# microcontrollerOptical.net
KiCad netlist of a schematic drawn in Altium Designer
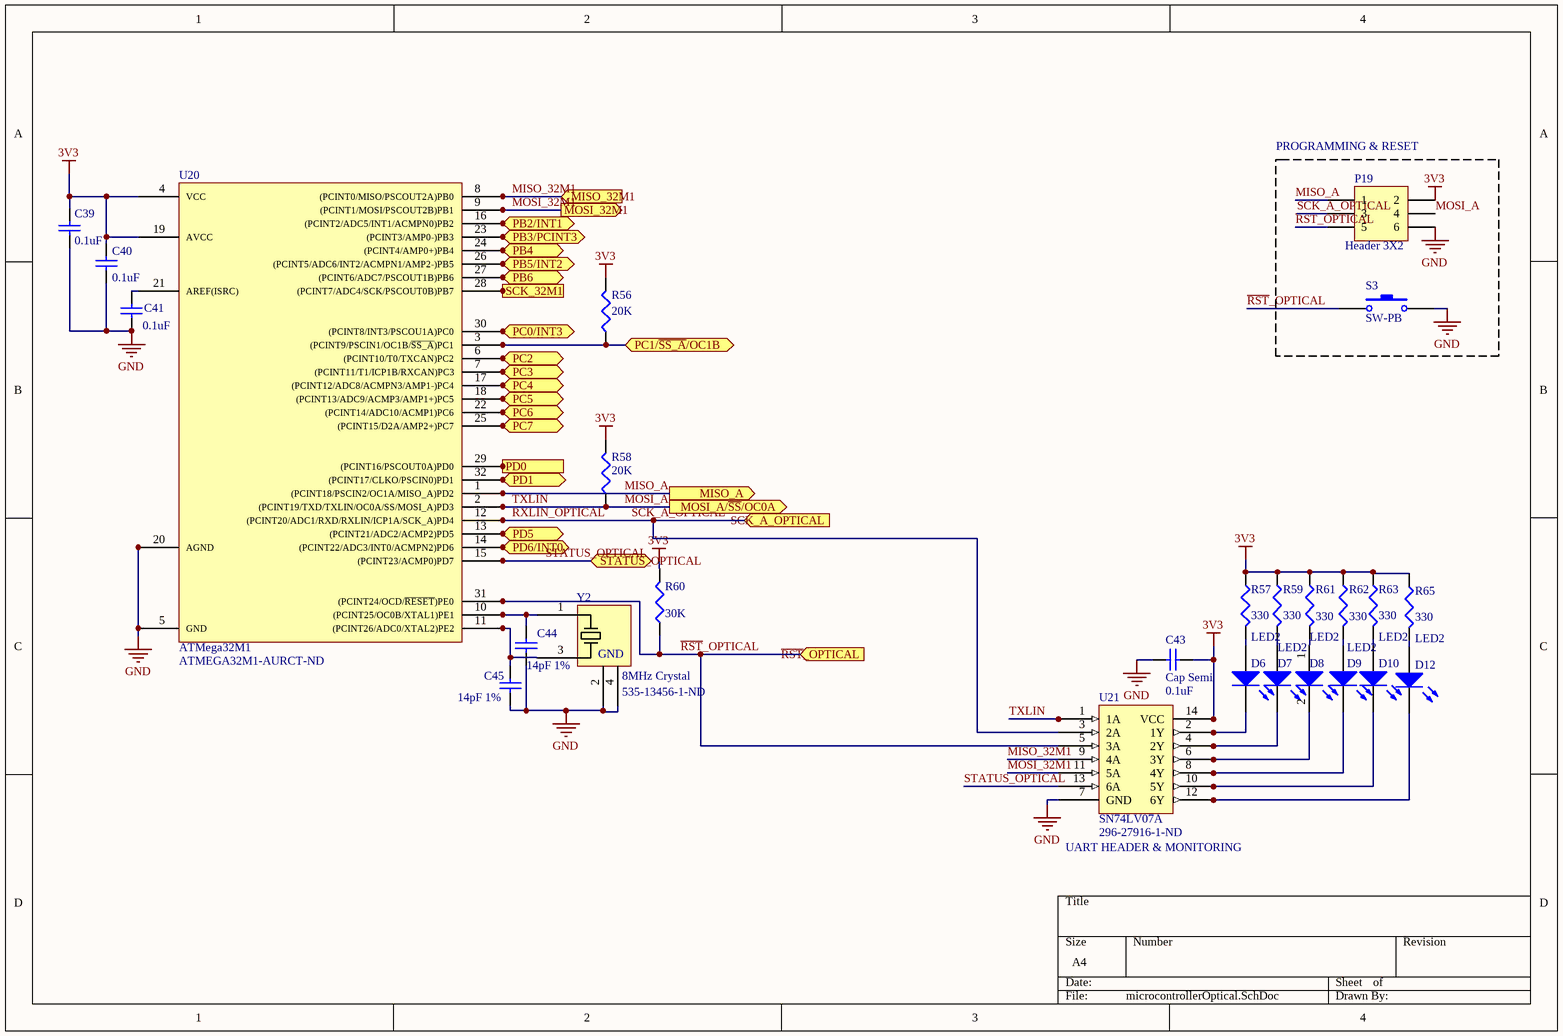
[diagram p0: microcontrollerOptical.SchDoc]

(export (version "E")
  (design (tool "Eeschema 10.0.6"))
  (components
    (comp (ref "C39")
      (value "0.1uF")
      (footprint "1608[0603]")
      (description "Capacitor (Semiconductor SIM Model)")
      (fields (field (name "PUBLISHER") "Altium Limited"))
      (libsource (lib "Miscellaneous Devices") (part "Cap Semi"))
    )
    (comp (ref "C40")
      (value "0.1uF")
      (footprint "1608[0603]")
      (description "Capacitor (Semiconductor SIM Model)")
      (fields (field (name "PUBLISHER") "Altium Limited"))
      (libsource (lib "Miscellaneous Devices") (part "Cap Semi"))
    )
    (comp (ref "C41")
      (value "0.1uF")
      (footprint "1608[0603]")
      (description "Capacitor (Semiconductor SIM Model)")
      (fields (field (name "PUBLISHER") "Altium Limited"))
      (libsource (lib "Miscellaneous Devices") (part "Cap Semi"))
    )
    (comp (ref "C43")
      (value "Cap Semi")
      (footprint "1608[0603]")
      (description "Capacitor (Semiconductor SIM Model)")
      (fields (field (name "ALTIUM_VALUE") "0.1uF") (field (name "PUBLISHER") "Altium Limited"))
      (libsource (lib "Miscellaneous Devices") (part "Cap Semi"))
    )
    (comp (ref "C44")
      (value "14pF 1%")
      (footprint "1608[0603]")
      (description "Capacitor (Semiconductor SIM Model)")
      (fields (field (name "Comment") "15pF 1%") (field (name "PUBLISHER") "Altium Limited"))
      (libsource (lib "Miscellaneous Devices") (part "Cap Semi"))
    )
    (comp (ref "C45")
      (value "14pF 1%")
      (footprint "1608[0603]")
      (description "Capacitor (Semiconductor SIM Model)")
      (fields (field (name "Comment") "15pF 1%") (field (name "PUBLISHER") "Altium Limited"))
      (libsource (lib "Miscellaneous Devices") (part "Cap Semi"))
    )
    (comp (ref "D6")
      (value "LED2")
      (footprint "0603-LED")
      (description "Typical RED, GREEN, YELLOW, AMBER GaAs LED")
      (fields (field (name "PUBLISHER") "Altium Limited"))
      (libsource (lib "") (part "LED2_1"))
    )
    (comp (ref "D7")
      (value "LED2")
      (footprint "0603-LED")
      (description "Typical RED, GREEN, YELLOW, AMBER GaAs LED")
      (fields (field (name "PUBLISHER") "Altium Limited"))
      (libsource (lib "") (part "LED2_1"))
    )
    (comp (ref "D8")
      (value "LED2")
      (footprint "0603-LED")
      (description "Typical RED, GREEN, YELLOW, AMBER GaAs LED")
      (fields (field (name "PUBLISHER") "Altium Limited"))
      (libsource (lib "Miscellaneous Devices") (part "LED2"))
    )
    (comp (ref "D9")
      (value "LED2")
      (footprint "0603-LED")
      (description "Typical RED, GREEN, YELLOW, AMBER GaAs LED")
      (fields (field (name "PUBLISHER") "Altium Limited"))
      (libsource (lib "") (part "LED2_1"))
    )
    (comp (ref "D10")
      (value "LED2")
      (footprint "0603-LED")
      (description "Typical RED, GREEN, YELLOW, AMBER GaAs LED")
      (fields (field (name "PUBLISHER") "Altium Limited"))
      (libsource (lib "") (part "LED2_1"))
    )
    (comp (ref "D12")
      (value "LED2")
      (footprint "0603-LED")
      (description "Typical RED, GREEN, YELLOW, AMBER GaAs LED")
      (fields (field (name "PUBLISHER") "Altium Limited"))
      (libsource (lib "") (part "LED2_1"))
    )
    (comp (ref "P19")
      (value "Header 3X2")
      (footprint "HDR2X3")
      (description "Header, 3-Pin, Dual row")
      (fields (field (name "PUBLISHER") "Altium Limited"))
      (libsource (lib "Miscellaneous Connectors") (part "Header 3X2"))
    )
    (comp (ref "R56")
      (value "20K")
      (footprint "J1-0603")
      (description "Resistor")
      (fields (field (name "PUBLISHER") "Altium Limited"))
      (libsource (lib "Miscellaneous Devices") (part "Res3"))
    )
    (comp (ref "R57")
      (value "330")
      (footprint "J1-0603")
      (description "Resistor")
      (fields (field (name "PUBLISHER") "Altium Limited"))
      (libsource (lib "Miscellaneous Devices") (part "Res3"))
    )
    (comp (ref "R58")
      (value "20K")
      (footprint "J1-0603")
      (description "Resistor")
      (fields (field (name "PUBLISHER") "Altium Limited"))
      (libsource (lib "Miscellaneous Devices") (part "Res3"))
    )
    (comp (ref "R59")
      (value "330")
      (footprint "J1-0603")
      (description "Resistor")
      (fields (field (name "PUBLISHER") "Altium Limited"))
      (libsource (lib "Miscellaneous Devices") (part "Res3"))
    )
    (comp (ref "R60")
      (value "30K")
      (footprint "J1-0603")
      (description "Resistor")
      (fields (field (name "PUBLISHER") "Altium Limited"))
      (libsource (lib "Miscellaneous Devices") (part "Res3"))
    )
    (comp (ref "R61")
      (value "330")
      (footprint "J1-0603")
      (description "Resistor")
      (fields (field (name "PUBLISHER") "Altium Limited"))
      (libsource (lib "Miscellaneous Devices") (part "Res3"))
    )
    (comp (ref "R62")
      (value "330")
      (footprint "J1-0603")
      (description "Resistor")
      (fields (field (name "PUBLISHER") "Altium Limited"))
      (libsource (lib "Miscellaneous Devices") (part "Res3"))
    )
    (comp (ref "R63")
      (value "330")
      (footprint "J1-0603")
      (description "Resistor")
      (fields (field (name "PUBLISHER") "Altium Limited"))
      (libsource (lib "Miscellaneous Devices") (part "Res3"))
    )
    (comp (ref "R65")
      (value "330")
      (footprint "J1-0603")
      (description "Resistor")
      (fields (field (name "PUBLISHER") "Altium Limited"))
      (libsource (lib "Miscellaneous Devices") (part "Res3"))
    )
    (comp (ref "S3")
      (value "SW-PB")
      (footprint "Pushbutton")
      (description "Switch")
      (fields (field (name "PUBLISHER") "Altium Limited"))
      (libsource (lib "Miscellaneous Devices") (part "SW-PB"))
    )
    (comp (ref "U20")
      (value "ATMega32M1")
      (footprint "QFP80P900X900X120-32N")
      (description "Atmel 8-bit AVR microcontroller.")
      (fields (field (name "SUPPLIER PART NUMBER 1") "ATMEGA32M1-AURCT-ND"))
      (libsource (lib "ICs") (part "ATMega32M1"))
    )
    (comp (ref "U21")
      (value "SN74LV07A")
      (footprint "SOP65P640X120-14N")
      (description "Six element 1-bit non-inverting open-drain buffer.")
      (fields (field (name "SUPPLIER PART NUMBER") "296-27916-1-ND"))
      (libsource (lib "ICs") (part "SN74LV07A"))
    )
    (comp (ref "Y2")
      (value "8MHz Crystal")
      (footprint "OSCSC500X320X110-4N")
      (description "8MHz Abracom 4-pin crystal.")
      (fields (field (name "SUPPLIER PART NUMBER 1") "535-13456-1-ND"))
      (libsource (lib "ICs") (part "8MHz Abracom 4-Pin Crystal"))
    )
  )
  (nets
    (net (code "1") (name "/MISO_32M1") (class "Default")
      (node (ref "U20") (pin "8") (pinfunction "(PCINT0/MISO/PSCOUT2A)PB0_8") (pintype "passive"))
      (node (ref "U21") (pin "9") (pinfunction "4A_9") (pintype "input"))
    )
    (net (code "2") (name "/MISO_A") (class "Default")
      (node (ref "P19") (pin "1") (pinfunction "1_1") (pintype "passive"))
      (node (ref "U20") (pin "1") (pinfunction "(PCINT18/PSCIN2/OC1A/MISO_A)PD2_1") (pintype "passive"))
    )
    (net (code "3") (name "/MOSI_32M1") (class "Default")
      (node (ref "U20") (pin "9") (pinfunction "(PCINT1/MOSI/PSCOUT2B)PB1_9") (pintype "passive"))
      (node (ref "U21") (pin "11") (pinfunction "5A_11") (pintype "input"))
    )
    (net (code "4") (name "/MOSI_A") (class "Default")
      (node (ref "P19") (pin "4") (pinfunction "4_4") (pintype "passive"))
      (node (ref "R58") (pin "1") (pinfunction "1_1") (pintype "passive"))
      (node (ref "U20") (pin "2") (pinfunction "(PCINT19/TXD/TXLIN/OC0A/SS/MOSI_A)PD3_2") (pintype "passive"))
      (node (ref "U21") (pin "1") (pinfunction "1A_1") (pintype "input"))
    )
    (net (code "5") (name "/PB2{slash}INT1") (class "Default")
      (node (ref "U20") (pin "16") (pinfunction "(PCINT2/ADC5/INT1/ACMPN0)PB2_16") (pintype "passive"))
    )
    (net (code "6") (name "/PB3{slash}PCINT3") (class "Default")
      (node (ref "U20") (pin "23") (pinfunction "(PCINT3/AMP0-)PB3_23") (pintype "passive"))
    )
    (net (code "7") (name "/PB4") (class "Default")
      (node (ref "U20") (pin "24") (pinfunction "(PCINT4/AMP0+)PB4_24") (pintype "passive"))
    )
    (net (code "8") (name "/PB5{slash}INT2") (class "Default")
      (node (ref "U20") (pin "26") (pinfunction "(PCINT5/ADC6/INT2/ACMPN1/AMP2-)PB5_26") (pintype "passive"))
    )
    (net (code "9") (name "/PB6") (class "Default")
      (node (ref "U20") (pin "27") (pinfunction "(PCINT6/ADC7/PSCOUT1B)PB6_27") (pintype "passive"))
    )
    (net (code "10") (name "/PC0{slash}INT3") (class "Default")
      (node (ref "U20") (pin "30") (pinfunction "(PCINT8/INT3/PSCOU1A)PC0_30") (pintype "passive"))
    )
    (net (code "11") (name "/PC1{slash}~{SS_A}{slash}OC1B") (class "Default")
      (node (ref "R56") (pin "1") (pinfunction "1_1") (pintype "passive"))
      (node (ref "U20") (pin "3") (pinfunction "(PCINT9/PSCIN1/OC1B/~{SS_A})PC1_3") (pintype "passive"))
    )
    (net (code "12") (name "/PC2") (class "Default")
      (node (ref "U20") (pin "6") (pinfunction "(PCINT10/T0/TXCAN)PC2_6") (pintype "passive"))
    )
    (net (code "13") (name "/PC3") (class "Default")
      (node (ref "U20") (pin "7") (pinfunction "(PCINT11/T1/ICP1B/RXCAN)PC3_7") (pintype "passive"))
    )
    (net (code "14") (name "/PC4") (class "Default")
      (node (ref "U20") (pin "17") (pinfunction "(PCINT12/ADC8/ACMPN3/AMP1-)PC4_17") (pintype "passive"))
    )
    (net (code "15") (name "/PC5") (class "Default")
      (node (ref "U20") (pin "18") (pinfunction "(PCINT13/ADC9/ACMP3/AMP1+)PC5_18") (pintype "passive"))
    )
    (net (code "16") (name "/PC6") (class "Default")
      (node (ref "U20") (pin "22") (pinfunction "(PCINT14/ADC10/ACMP1)PC6_22") (pintype "passive"))
    )
    (net (code "17") (name "/PC7") (class "Default")
      (node (ref "U20") (pin "25") (pinfunction "(PCINT15/D2A/AMP2+)PC7_25") (pintype "passive"))
    )
    (net (code "18") (name "/PD0") (class "Default")
      (node (ref "U20") (pin "29") (pinfunction "(PCINT16/PSCOUT0A)PD0_29") (pintype "passive"))
    )
    (net (code "19") (name "/PD1") (class "Default")
      (node (ref "U20") (pin "32") (pinfunction "(PCINT17/CLKO/PSCIN0)PD1_32") (pintype "passive"))
    )
    (net (code "20") (name "/PD5") (class "Default")
      (node (ref "U20") (pin "13") (pinfunction "(PCINT21/ADC2/ACMP2)PD5_13") (pintype "passive"))
    )
    (net (code "21") (name "/PD6{slash}INT0") (class "Default")
      (node (ref "U20") (pin "14") (pinfunction "(PCINT22/ADC3/INT0/ACMPN2)PD6_14") (pintype "passive"))
    )
    (net (code "22") (name "/RXLIN_OPTICAL") (class "Default")
      (node (ref "P19") (pin "3") (pinfunction "3_3") (pintype "passive"))
      (node (ref "U20") (pin "12") (pinfunction "(PCINT20/ADC1/RXD/RXLIN/ICP1A/SCK_A)PD4_12") (pintype "passive"))
      (node (ref "U21") (pin "3") (pinfunction "2A_3") (pintype "input"))
    )
    (net (code "23") (name "/SCK_32M1") (class "Default")
      (node (ref "U20") (pin "28") (pinfunction "(PCINT7/ADC4/SCK/PSCOUT0B)PB7_28") (pintype "passive"))
    )
    (net (code "24") (name "/STATUS_OPTICAL") (class "Default")
      (node (ref "U20") (pin "15") (pinfunction "(PCINT23/ACMP0)PD7_15") (pintype "passive"))
      (node (ref "U21") (pin "13") (pinfunction "6A_13") (pintype "input"))
    )
    (net (code "25") (name "/~{RST}_OPTICAL") (class "Default")
      (node (ref "P19") (pin "5") (pinfunction "5_5") (pintype "passive"))
      (node (ref "R60") (pin "1") (pinfunction "1_1") (pintype "passive"))
      (node (ref "S3") (pin "1") (pinfunction "1_1") (pintype "passive"))
      (node (ref "U20") (pin "31") (pinfunction "(PCINT24/OCD/~{RESET})PE0_31") (pintype "passive"))
      (node (ref "U21") (pin "5") (pinfunction "3A_5") (pintype "input"))
    )
    (net (code "26") (name "3V3") (class "Default")
      (node (ref "C39") (pin "2") (pinfunction "2_2") (pintype "passive"))
      (node (ref "C40") (pin "2") (pinfunction "2_2") (pintype "passive"))
      (node (ref "C43") (pin "2") (pinfunction "2_2") (pintype "passive"))
      (node (ref "P19") (pin "2") (pinfunction "2_2") (pintype "passive"))
      (node (ref "R56") (pin "2") (pinfunction "2_2") (pintype "passive"))
      (node (ref "R57") (pin "1") (pinfunction "1_1") (pintype "passive"))
      (node (ref "R58") (pin "2") (pinfunction "2_2") (pintype "passive"))
      (node (ref "R59") (pin "1") (pinfunction "1_1") (pintype "passive"))
      (node (ref "R60") (pin "2") (pinfunction "2_2") (pintype "passive"))
      (node (ref "R61") (pin "1") (pinfunction "1_1") (pintype "passive"))
      (node (ref "R62") (pin "1") (pinfunction "1_1") (pintype "passive"))
      (node (ref "R63") (pin "1") (pinfunction "1_1") (pintype "passive"))
      (node (ref "R65") (pin "1") (pinfunction "1_1") (pintype "passive"))
      (node (ref "U20") (pin "19") (pinfunction "AVCC_19") (pintype "passive"))
      (node (ref "U20") (pin "4") (pinfunction "VCC_4") (pintype "passive"))
      (node (ref "U21") (pin "14") (pinfunction "VCC_14") (pintype "power_in"))
    )
    (net (code "27") (name "GND") (class "Default")
      (node (ref "C39") (pin "1") (pinfunction "1_1") (pintype "passive"))
      (node (ref "C40") (pin "1") (pinfunction "1_1") (pintype "passive"))
      (node (ref "C41") (pin "2") (pinfunction "2_2") (pintype "passive"))
      (node (ref "C43") (pin "1") (pinfunction "1_1") (pintype "passive"))
      (node (ref "C44") (pin "1") (pinfunction "1_1") (pintype "passive"))
      (node (ref "C45") (pin "1") (pinfunction "1_1") (pintype "passive"))
      (node (ref "P19") (pin "6") (pinfunction "6_6") (pintype "passive"))
      (node (ref "S3") (pin "2") (pinfunction "2_2") (pintype "passive"))
      (node (ref "U20") (pin "20") (pinfunction "AGND_20") (pintype "passive"))
      (node (ref "U20") (pin "5") (pinfunction "GND_5") (pintype "passive"))
      (node (ref "U21") (pin "7") (pinfunction "GND_7") (pintype "power_in"))
      (node (ref "Y2") (pin "2") (pinfunction "5_2") (pintype "passive"))
      (node (ref "Y2") (pin "4") (pinfunction "4_4") (pintype "passive"))
    )
    (net (code "28") (name "Net-(D6-A)") (class "Default")
      (node (ref "D6") (pin "1") (pinfunction "A_1") (pintype "passive"))
      (node (ref "R57") (pin "2") (pinfunction "2_2") (pintype "passive"))
    )
    (net (code "29") (name "Net-(D6-K)") (class "Default")
      (node (ref "D6") (pin "2") (pinfunction "K_2") (pintype "passive"))
      (node (ref "U21") (pin "2") (pinfunction "1Y_2") (pintype "output"))
    )
    (net (code "30") (name "Net-(D7-A)") (class "Default")
      (node (ref "D7") (pin "1") (pinfunction "A_1") (pintype "passive"))
      (node (ref "R59") (pin "2") (pinfunction "2_2") (pintype "passive"))
    )
    (net (code "31") (name "Net-(D7-K)") (class "Default")
      (node (ref "D7") (pin "2") (pinfunction "K_2") (pintype "passive"))
      (node (ref "U21") (pin "4") (pinfunction "2Y_4") (pintype "output"))
    )
    (net (code "32") (name "Net-(D8-A)") (class "Default")
      (node (ref "D8") (pin "1") (pinfunction "A_1") (pintype "passive"))
      (node (ref "R61") (pin "2") (pinfunction "2_2") (pintype "passive"))
    )
    (net (code "33") (name "Net-(D8-K)") (class "Default")
      (node (ref "D8") (pin "2") (pinfunction "K_2") (pintype "passive"))
      (node (ref "U21") (pin "6") (pinfunction "3Y_6") (pintype "output"))
    )
    (net (code "34") (name "Net-(D9-A)") (class "Default")
      (node (ref "D9") (pin "1") (pinfunction "A_1") (pintype "passive"))
      (node (ref "R62") (pin "2") (pinfunction "2_2") (pintype "passive"))
    )
    (net (code "35") (name "Net-(D9-K)") (class "Default")
      (node (ref "D9") (pin "2") (pinfunction "K_2") (pintype "passive"))
      (node (ref "U21") (pin "8") (pinfunction "4Y_8") (pintype "output"))
    )
    (net (code "36") (name "Net-(D10-A)") (class "Default")
      (node (ref "D10") (pin "1") (pinfunction "A_1") (pintype "passive"))
      (node (ref "R63") (pin "2") (pinfunction "2_2") (pintype "passive"))
    )
    (net (code "37") (name "Net-(D10-K)") (class "Default")
      (node (ref "D10") (pin "2") (pinfunction "K_2") (pintype "passive"))
      (node (ref "U21") (pin "10") (pinfunction "5Y_10") (pintype "output"))
    )
    (net (code "38") (name "Net-(D12-A)") (class "Default")
      (node (ref "D12") (pin "1") (pinfunction "A_1") (pintype "passive"))
      (node (ref "R65") (pin "2") (pinfunction "2_2") (pintype "passive"))
    )
    (net (code "39") (name "Net-(D12-K)") (class "Default")
      (node (ref "D12") (pin "2") (pinfunction "K_2") (pintype "passive"))
      (node (ref "U21") (pin "12") (pinfunction "6Y_12") (pintype "output"))
    )
    (net (code "40") (name "Net-(U20-(PCINT25{slash}OC0B{slash}XTAL1)PE1)") (class "Default")
      (node (ref "C44") (pin "2") (pinfunction "2_2") (pintype "passive"))
      (node (ref "U20") (pin "10") (pinfunction "(PCINT25/OC0B/XTAL1)PE1_10") (pintype "passive"))
      (node (ref "Y2") (pin "1") (pinfunction "IN_1") (pintype "passive"))
    )
    (net (code "41") (name "Net-(U20-(PCINT26{slash}ADC0{slash}XTAL2)PE2)") (class "Default")
      (node (ref "C45") (pin "2") (pinfunction "2_2") (pintype "passive"))
      (node (ref "U20") (pin "11") (pinfunction "(PCINT26/ADC0/XTAL2)PE2_11") (pintype "passive"))
      (node (ref "Y2") (pin "3") (pinfunction "IN_3") (pintype "passive"))
    )
    (net (code "42") (name "Net-(U20-AREF(ISRC))") (class "Default")
      (node (ref "C41") (pin "1") (pinfunction "1_1") (pintype "passive"))
      (node (ref "U20") (pin "21") (pinfunction "AREF(ISRC)_21") (pintype "passive"))
    )
  )
)
